# GSM.net
KiCad netlist of a schematic drawn in Altium Designer
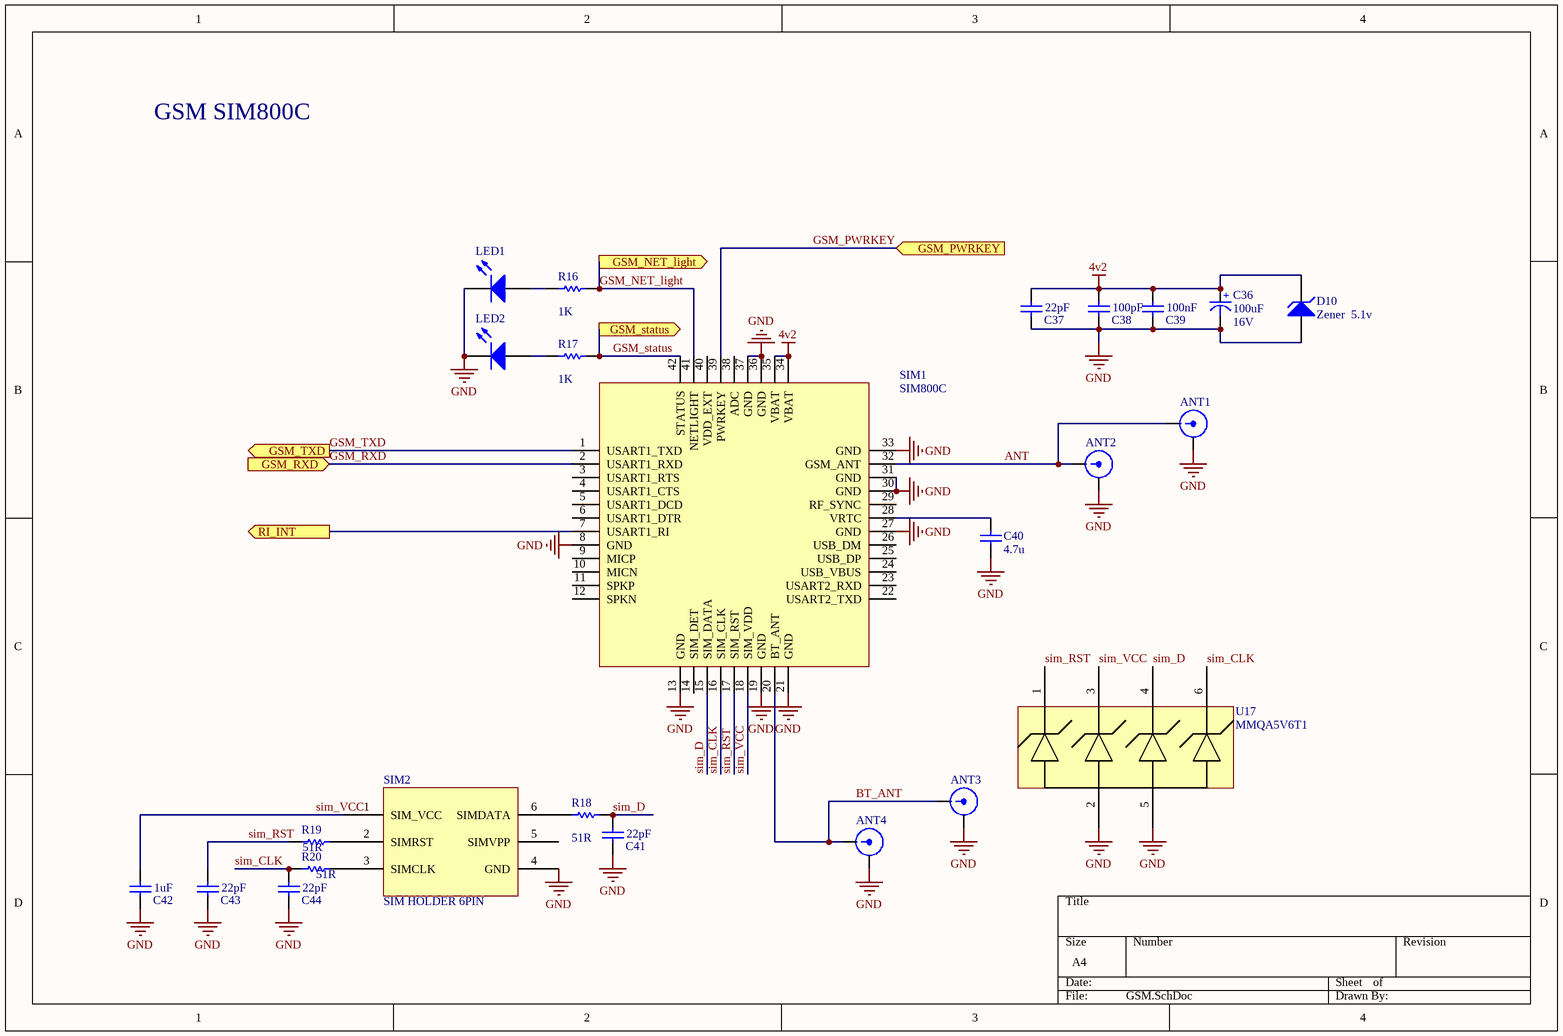
[diagram p0: GSM.SchDoc]

(export (version "E")
  (design (tool "Eeschema 10.0.6"))
  (components
    (comp (ref "ANT1")
      (value "Antenna UFL")
      (footprint "UFL ant")
      (description "Antenna")
      (fields (field (name "DESIGNER") "Ali Hafizi"))
      (libsource (lib "Altium (2)") (part "ANT SMA"))
    )
    (comp (ref "ANT2")
      (value "Antenna SMA")
      (footprint "SMA")
      (description "Antenna")
      (fields (field (name "DESIGNER") "Ali Hafizi"))
      (libsource (lib "Altium (2)") (part "ANT SMA"))
    )
    (comp (ref "ANT3")
      (value "Antenna UFL")
      (footprint "UFL ant")
      (description "Antenna")
      (fields (field (name "DESIGNER") "Ali Hafizi"))
      (libsource (lib "Altium (2)") (part "ANT SMA"))
    )
    (comp (ref "ANT4")
      (value "Antenna SMA")
      (footprint "SMA")
      (description "Antenna")
      (fields (field (name "DESIGNER") "Ali Hafizi"))
      (libsource (lib "Altium (2)") (part "ANT SMA"))
    )
    (comp (ref "C36")
      (value "100uF")
      (footprint "Cap 1206 (3216X18L) Size A")
      (description "Tantal Capacitor Size A")
      (fields
        (field (name "VOLTAGE") "16V")
        (field (name "Comment") "cap 100uF")
        (field (name "DESIGNER") "Saeid Jorablo")
      )
      (libsource (lib "My Library") (part "Cap-Polar"))
    )
    (comp (ref "C37")
      (value "22pF")
      (footprint "Cap 805")
      (description "Capacitor")
      (fields (field (name "Comment") "cap 22pF"))
      (libsource (lib "Altium library (www.AVRelec.com)") (part "Cap ceramic"))
    )
    (comp (ref "C38")
      (value "100pF")
      (footprint "Cap 805")
      (description "Capacitor")
      (fields (field (name "Comment") "cap 100pF"))
      (libsource (lib "Altium library (www.AVRelec.com)") (part "Cap ceramic"))
    )
    (comp (ref "C39")
      (value "100nF")
      (footprint "Cap 805")
      (description "Capacitor")
      (fields (field (name "Comment") "cap 100nF"))
      (libsource (lib "Altium library (www.AVRelec.com)") (part "Cap ceramic"))
    )
    (comp (ref "C40")
      (value "4.7u")
      (footprint "Cap 805")
      (description "Capacitor")
      (fields (field (name "Comment") "cap 4.7u"))
      (libsource (lib "Altium library (www.AVRelec.com)") (part "Cap ceramic"))
    )
    (comp (ref "C41")
      (value "22pF")
      (footprint "Cap 805")
      (description "Capacitor")
      (fields (field (name "Comment") "cap 22pF"))
      (libsource (lib "Altium library (www.AVRelec.com)") (part "Cap ceramic"))
    )
    (comp (ref "C42")
      (value "1uF")
      (footprint "Cap 805")
      (description "Capacitor")
      (fields (field (name "Comment") "cap 1uF"))
      (libsource (lib "Altium library (www.AVRelec.com)") (part "Cap ceramic"))
    )
    (comp (ref "C43")
      (value "22pF")
      (footprint "Cap 805")
      (description "Capacitor")
      (fields (field (name "Comment") "cap 22pF"))
      (libsource (lib "Altium library (www.AVRelec.com)") (part "Cap ceramic"))
    )
    (comp (ref "C44")
      (value "22pF")
      (footprint "Cap 805")
      (description "Capacitor")
      (fields (field (name "Comment") "cap 22pF"))
      (libsource (lib "Altium library (www.AVRelec.com)") (part "Cap ceramic"))
    )
    (comp (ref "D10")
      (value "Zener  5.1v")
      (footprint "Diode 1n4148 SMD")
      (description "Zener Diode")
      (fields (field (name "PUBLISHER") "Altium Limited"))
      (libsource (lib "Miscellaneous Devices") (part "D Zener"))
    )
    (comp (ref "LED1")
      (value "LED Green")
      (footprint "0805-LED")
      (description "LED SMD")
      (fields (field (name "PUBLISHER") "Altium Limited"))
      (libsource (lib "Altium library (www.AVRelec.com)") (part "LED"))
    )
    (comp (ref "LED2")
      (value "LED Red")
      (footprint "0805-LED")
      (description "LED SMD")
      (fields (field (name "PUBLISHER") "Altium Limited"))
      (libsource (lib "Altium library (www.AVRelec.com)") (part "LED"))
    )
    (comp (ref "R16")
      (value "1K")
      (footprint "RES 0805 (2012X06L)")
      (description "Resistor")
      (fields (field (name "Comment") "Res 1K") (field (name "PUBLISHER") "Altium Limited"))
      (libsource (lib "Miscellaneous Devices") (part "Res1"))
    )
    (comp (ref "R17")
      (value "1K")
      (footprint "RES 0805 (2012X06L)")
      (description "Resistor")
      (fields (field (name "Comment") "Res 1K") (field (name "PUBLISHER") "Altium Limited"))
      (libsource (lib "Miscellaneous Devices") (part "Res1"))
    )
    (comp (ref "R18")
      (value "51R")
      (footprint "RES 0805 (2012X06L)")
      (description "Resistor")
      (fields (field (name "Comment") "Res 51R") (field (name "PUBLISHER") "Altium Limited"))
      (libsource (lib "Miscellaneous Devices") (part "Res1"))
    )
    (comp (ref "R19")
      (value "51R")
      (footprint "RES 0805 (2012X06L)")
      (description "Resistor")
      (fields (field (name "Comment") "Res 51R") (field (name "PUBLISHER") "Altium Limited"))
      (libsource (lib "Miscellaneous Devices") (part "Res1"))
    )
    (comp (ref "R20")
      (value "51R")
      (footprint "RES 0805 (2012X06L)")
      (description "Resistor")
      (fields (field (name "Comment") "Res 51R") (field (name "PUBLISHER") "Altium Limited"))
      (libsource (lib "Miscellaneous Devices") (part "Res1"))
    )
    (comp (ref "SIM1")
      (value "SIM800C")
      (footprint "SIM800C")
      (description "GSM Module")
      (fields (field (name "DESIGNER") "Ali Hafizi"))
      (libsource (lib "Altium (2)") (part "SIM800C"))
    )
    (comp (ref "SIM2")
      (value "SIM HOLDER 6PIN")
      (footprint "simcard_holder")
      (description "SIM HOLDER")
      (libsource (lib "Altium (2)") (part "SIM HOLDER"))
    )
    (comp (ref "U17")
      (value "MMQA5V6T1")
      (footprint "SOT23-6")
      (description "TVS diode ESD protection")
      (libsource (lib "Schlib1") (part "MMQA5V6T1"))
    )
  )
  (nets
    (net (code "1") (name "/ANT") (class "Default")
      (node (ref "ANT1") (pin "1") (pinfunction "1_1") (pintype "passive"))
      (node (ref "ANT2") (pin "1") (pinfunction "1_1") (pintype "passive"))
      (node (ref "SIM1") (pin "32") (pinfunction "GSM_ANT_32") (pintype "passive"))
    )
    (net (code "2") (name "/BT_ANT") (class "Default")
      (node (ref "ANT3") (pin "1") (pinfunction "1_1") (pintype "passive"))
      (node (ref "ANT4") (pin "1") (pinfunction "1_1") (pintype "passive"))
      (node (ref "SIM1") (pin "20") (pinfunction "BT_ANT_20") (pintype "passive"))
    )
    (net (code "3") (name "/GSM_NET_light") (class "Default")
      (node (ref "R16") (pin "1") (pinfunction "1_1") (pintype "passive"))
      (node (ref "SIM1") (pin "41") (pinfunction "NETLIGHT_41") (pintype "passive"))
    )
    (net (code "4") (name "/GSM_PWRKEY") (class "Default")
      (node (ref "SIM1") (pin "39") (pinfunction "PWRKEY_39") (pintype "passive"))
    )
    (net (code "5") (name "/GSM_RXD") (class "Default")
      (node (ref "SIM1") (pin "2") (pinfunction "USART1_RXD_2") (pintype "passive"))
    )
    (net (code "6") (name "/GSM_TXD") (class "Default")
      (node (ref "SIM1") (pin "1") (pinfunction "USART1_TXD_1") (pintype "passive"))
    )
    (net (code "7") (name "/GSM_status") (class "Default")
      (node (ref "R17") (pin "1") (pinfunction "1_1") (pintype "passive"))
      (node (ref "SIM1") (pin "42") (pinfunction "STATUS_42") (pintype "passive"))
    )
    (net (code "8") (name "/RI_INT") (class "Default")
      (node (ref "SIM1") (pin "7") (pinfunction "USART1_RI_7") (pintype "passive"))
    )
    (net (code "9") (name "/sim_CLK") (class "Default")
      (node (ref "C44") (pin "2") (pinfunction "2_2") (pintype "passive"))
      (node (ref "R20") (pin "1") (pinfunction "1_1") (pintype "passive"))
      (node (ref "SIM1") (pin "16") (pinfunction "SIM_CLK_16") (pintype "passive"))
      (node (ref "U17") (pin "6") (pinfunction "Cathode_6") (pintype "passive"))
    )
    (net (code "10") (name "/sim_D") (class "Default")
      (node (ref "C41") (pin "2") (pinfunction "2_2") (pintype "passive"))
      (node (ref "R18") (pin "2") (pinfunction "2_2") (pintype "passive"))
      (node (ref "SIM1") (pin "15") (pinfunction "SIM_DATA_15") (pintype "passive"))
      (node (ref "U17") (pin "4") (pinfunction "Cathode_4") (pintype "passive"))
    )
    (net (code "11") (name "/sim_RST") (class "Default")
      (node (ref "C43") (pin "2") (pinfunction "2_2") (pintype "passive"))
      (node (ref "R19") (pin "1") (pinfunction "1_1") (pintype "passive"))
      (node (ref "SIM1") (pin "17") (pinfunction "SIM_RST_17") (pintype "passive"))
      (node (ref "U17") (pin "1") (pinfunction "Cathode_1") (pintype "passive"))
    )
    (net (code "12") (name "/sim_VCC") (class "Default")
      (node (ref "C42") (pin "2") (pinfunction "2_2") (pintype "passive"))
      (node (ref "SIM1") (pin "18") (pinfunction "SIM_VDD_18") (pintype "passive"))
      (node (ref "SIM2") (pin "1") (pinfunction "SIM_VCC_1") (pintype "passive"))
      (node (ref "U17") (pin "3") (pinfunction "Cathode_3") (pintype "passive"))
    )
    (net (code "13") (name "4v2") (class "Default")
      (node (ref "C36") (pin "1") (pinfunction "+_1") (pintype "passive"))
      (node (ref "C37") (pin "2") (pinfunction "2_2") (pintype "passive"))
      (node (ref "C38") (pin "2") (pinfunction "2_2") (pintype "passive"))
      (node (ref "C39") (pin "2") (pinfunction "2_2") (pintype "passive"))
      (node (ref "D10") (pin "2") (pinfunction "K_2") (pintype "passive"))
      (node (ref "SIM1") (pin "34") (pinfunction "VBAT_34") (pintype "passive"))
      (node (ref "SIM1") (pin "35") (pinfunction "VBAT_35") (pintype "passive"))
    )
    (net (code "14") (name "GND") (class "Default")
      (node (ref "ANT1") (pin "2") (pinfunction "2_2") (pintype "passive"))
      (node (ref "ANT2") (pin "2") (pinfunction "2_2") (pintype "passive"))
      (node (ref "ANT3") (pin "2") (pinfunction "2_2") (pintype "passive"))
      (node (ref "ANT4") (pin "2") (pinfunction "2_2") (pintype "passive"))
      (node (ref "C36") (pin "2") (pinfunction "-_2") (pintype "passive"))
      (node (ref "C37") (pin "1") (pinfunction "1_1") (pintype "passive"))
      (node (ref "C38") (pin "1") (pinfunction "1_1") (pintype "passive"))
      (node (ref "C39") (pin "1") (pinfunction "1_1") (pintype "passive"))
      (node (ref "C40") (pin "1") (pinfunction "1_1") (pintype "passive"))
      (node (ref "C41") (pin "1") (pinfunction "1_1") (pintype "passive"))
      (node (ref "C42") (pin "1") (pinfunction "1_1") (pintype "passive"))
      (node (ref "C43") (pin "1") (pinfunction "1_1") (pintype "passive"))
      (node (ref "C44") (pin "1") (pinfunction "1_1") (pintype "passive"))
      (node (ref "D10") (pin "1") (pinfunction "A_1") (pintype "passive"))
      (node (ref "LED1") (pin "K") (pinfunction "K_K") (pintype "passive"))
      (node (ref "LED2") (pin "K") (pinfunction "K_K") (pintype "passive"))
      (node (ref "SIM1") (pin "13") (pinfunction "GND_13") (pintype "passive"))
      (node (ref "SIM1") (pin "19") (pinfunction "GND_19") (pintype "passive"))
      (node (ref "SIM1") (pin "21") (pinfunction "GND_21") (pintype "passive"))
      (node (ref "SIM1") (pin "27") (pinfunction "GND_27") (pintype "passive"))
      (node (ref "SIM1") (pin "30") (pinfunction "GND_30") (pintype "passive"))
      (node (ref "SIM1") (pin "31") (pinfunction "GND_31") (pintype "passive"))
      (node (ref "SIM1") (pin "33") (pinfunction "GND_33") (pintype "passive"))
      (node (ref "SIM1") (pin "36") (pinfunction "GND_36") (pintype "passive"))
      (node (ref "SIM1") (pin "37") (pinfunction "GND_37") (pintype "passive"))
      (node (ref "SIM1") (pin "8") (pinfunction "GND_8") (pintype "passive"))
      (node (ref "SIM2") (pin "4") (pinfunction "GND_4") (pintype "passive"))
      (node (ref "U17") (pin "2") (pinfunction "Cathode_2") (pintype "passive"))
      (node (ref "U17") (pin "5") (pinfunction "Cathode_5") (pintype "passive"))
    )
    (net (code "15") (name "Net-(LED1-PadA)") (class "Default")
      (node (ref "LED1") (pin "A") (pinfunction "A_A") (pintype "passive"))
      (node (ref "R16") (pin "2") (pinfunction "2_2") (pintype "passive"))
    )
    (net (code "16") (name "Net-(LED2-PadA)") (class "Default")
      (node (ref "LED2") (pin "A") (pinfunction "A_A") (pintype "passive"))
      (node (ref "R17") (pin "2") (pinfunction "2_2") (pintype "passive"))
    )
    (net (code "17") (name "Net-(SIM1-VRTC)") (class "Default")
      (node (ref "C40") (pin "2") (pinfunction "2_2") (pintype "passive"))
      (node (ref "SIM1") (pin "28") (pinfunction "VRTC_28") (pintype "passive"))
    )
    (net (code "18") (name "Net-(SIM2-SIMCLK)") (class "Default")
      (node (ref "R20") (pin "2") (pinfunction "2_2") (pintype "passive"))
      (node (ref "SIM2") (pin "3") (pinfunction "SIMCLK_3") (pintype "passive"))
    )
    (net (code "19") (name "Net-(SIM2-SIMDATA)") (class "Default")
      (node (ref "R18") (pin "1") (pinfunction "1_1") (pintype "passive"))
      (node (ref "SIM2") (pin "6") (pinfunction "SIMDATA_6") (pintype "passive"))
    )
    (net (code "20") (name "Net-(SIM2-SIMRST)") (class "Default")
      (node (ref "R19") (pin "2") (pinfunction "2_2") (pintype "passive"))
      (node (ref "SIM2") (pin "2") (pinfunction "SIMRST_2") (pintype "passive"))
    )
    (net (code "21") (name "unconnected-(SIM1-ADC-Pad38)") (class "Default")
      (node (ref "SIM1") (pin "38") (pinfunction "ADC_38") (pintype "passive"))
    )
    (net (code "22") (name "unconnected-(SIM1-MICN-Pad10)") (class "Default")
      (node (ref "SIM1") (pin "10") (pinfunction "MICN_10") (pintype "passive"))
    )
    (net (code "23") (name "unconnected-(SIM1-MICP-Pad9)") (class "Default")
      (node (ref "SIM1") (pin "9") (pinfunction "MICP_9") (pintype "passive"))
    )
    (net (code "24") (name "unconnected-(SIM1-RF_SYNC-Pad29)") (class "Default")
      (node (ref "SIM1") (pin "29") (pinfunction "RF_SYNC_29") (pintype "passive"))
    )
    (net (code "25") (name "unconnected-(SIM1-SIM_DET-Pad14)") (class "Default")
      (node (ref "SIM1") (pin "14") (pinfunction "SIM_DET_14") (pintype "passive"))
    )
    (net (code "26") (name "unconnected-(SIM1-SPKN-Pad12)") (class "Default")
      (node (ref "SIM1") (pin "12") (pinfunction "SPKN_12") (pintype "passive"))
    )
    (net (code "27") (name "unconnected-(SIM1-SPKP-Pad11)") (class "Default")
      (node (ref "SIM1") (pin "11") (pinfunction "SPKP_11") (pintype "passive"))
    )
    (net (code "28") (name "unconnected-(SIM1-USART1_CTS-Pad4)") (class "Default")
      (node (ref "SIM1") (pin "4") (pinfunction "USART1_CTS_4") (pintype "passive"))
    )
    (net (code "29") (name "unconnected-(SIM1-USART1_DCD-Pad5)") (class "Default")
      (node (ref "SIM1") (pin "5") (pinfunction "USART1_DCD_5") (pintype "passive"))
    )
    (net (code "30") (name "unconnected-(SIM1-USART1_DTR-Pad6)") (class "Default")
      (node (ref "SIM1") (pin "6") (pinfunction "USART1_DTR_6") (pintype "passive"))
    )
    (net (code "31") (name "unconnected-(SIM1-USART1_RTS-Pad3)") (class "Default")
      (node (ref "SIM1") (pin "3") (pinfunction "USART1_RTS_3") (pintype "passive"))
    )
    (net (code "32") (name "unconnected-(SIM1-USART2_RXD-Pad23)") (class "Default")
      (node (ref "SIM1") (pin "23") (pinfunction "USART2_RXD_23") (pintype "passive"))
    )
    (net (code "33") (name "unconnected-(SIM1-USART2_TXD-Pad22)") (class "Default")
      (node (ref "SIM1") (pin "22") (pinfunction "USART2_TXD_22") (pintype "passive"))
    )
    (net (code "34") (name "unconnected-(SIM1-USB_DM-Pad26)") (class "Default")
      (node (ref "SIM1") (pin "26") (pinfunction "USB_DM_26") (pintype "passive"))
    )
    (net (code "35") (name "unconnected-(SIM1-USB_DP-Pad25)") (class "Default")
      (node (ref "SIM1") (pin "25") (pinfunction "USB_DP_25") (pintype "passive"))
    )
    (net (code "36") (name "unconnected-(SIM1-USB_VBUS-Pad24)") (class "Default")
      (node (ref "SIM1") (pin "24") (pinfunction "USB_VBUS_24") (pintype "passive"))
    )
    (net (code "37") (name "unconnected-(SIM1-VDD_EXT-Pad40)") (class "Default")
      (node (ref "SIM1") (pin "40") (pinfunction "VDD_EXT_40") (pintype "passive"))
    )
    (net (code "38") (name "unconnected-(SIM2-SIMVPP-Pad5)") (class "Default")
      (node (ref "SIM2") (pin "5") (pinfunction "SIMVPP_5") (pintype "passive"))
    )
  )
)
